# TDS_sensor_2.net
KiCad netlist of a schematic drawn in Altium Designer
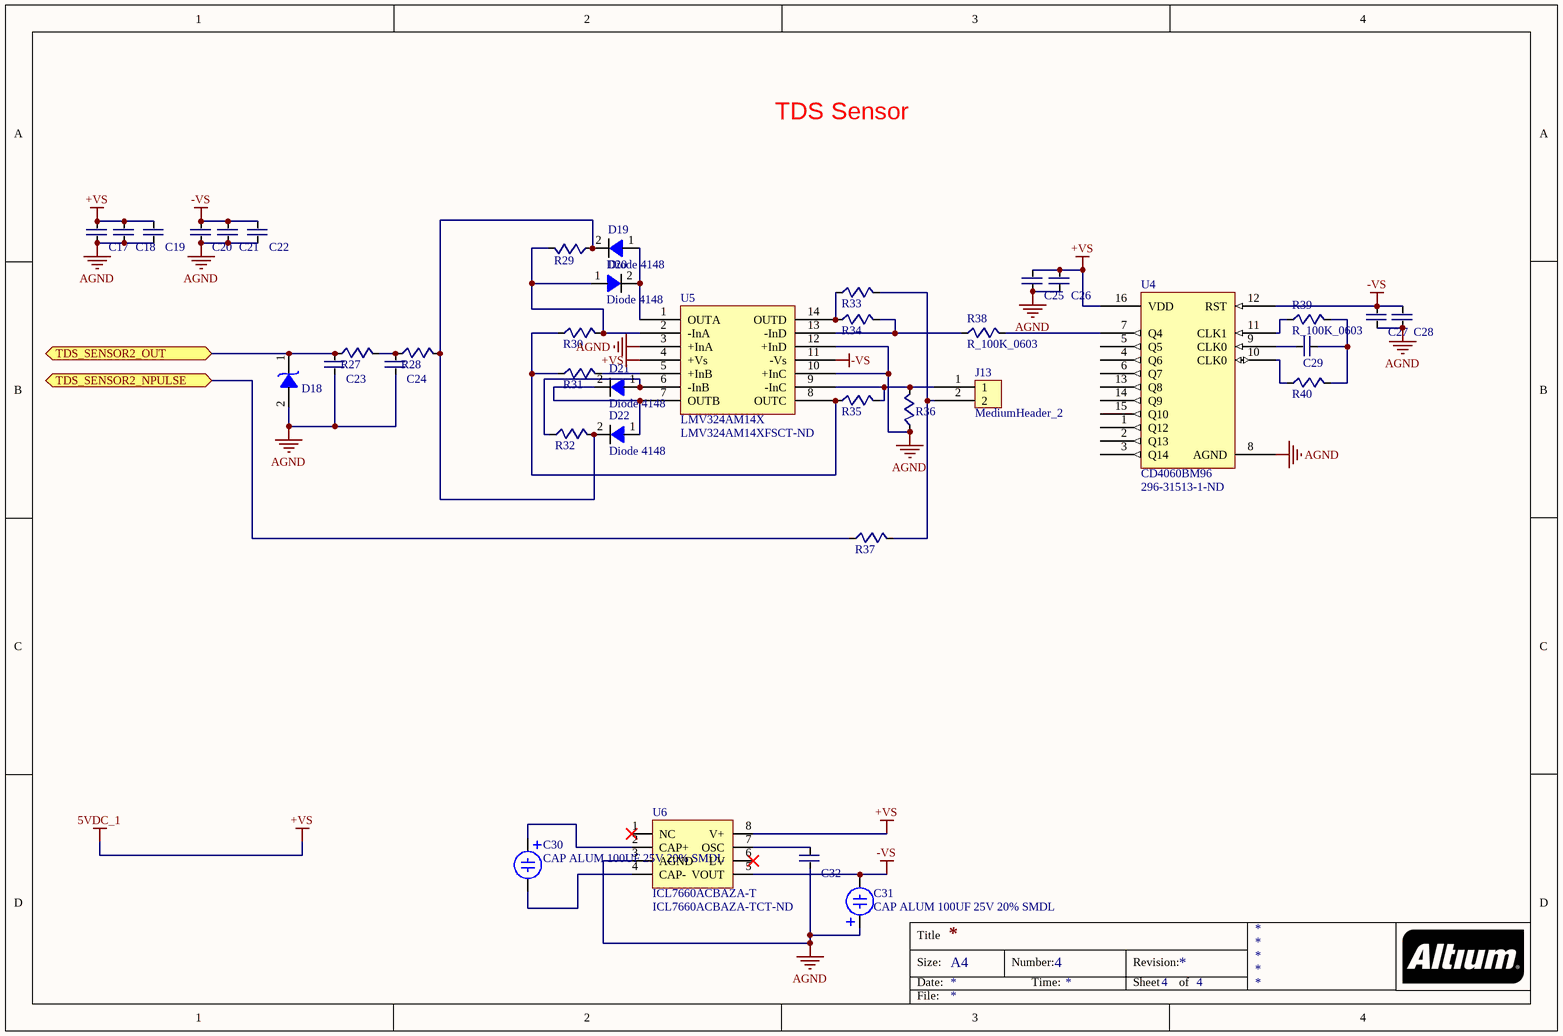
[diagram p0: TDS sensor 2.SchDoc]

(export (version "E")
  (design (tool "Eeschema 10.0.6"))
  (components
    (comp (ref "C17")
      (value "100n Cer")
      (footprint "CN-SMD-0805")
      (description "CAP CER 0.1UF 25V 10% X7R 0805")
      (libsource (lib "EngineersLife") (part "CAPC0805_104"))
    )
    (comp (ref "C18")
      (value "1n Cer")
      (footprint "CN-SMD-0805")
      (description "CAP CER 1000PF 50V 10% X7R 0805")
      (libsource (lib "EngineersLife") (part "CAPC0805_102"))
    )
    (comp (ref "C19")
      (value "10n Cer")
      (footprint "CN-SMD-0805")
      (description "CAP CER 10000PF 100V X7R 0805")
      (libsource (lib "EngineersLife") (part "CAPC0805_103"))
    )
    (comp (ref "C20")
      (value "100n Cer")
      (footprint "CN-SMD-0805")
      (description "CAP CER 0.1UF 25V 10% X7R 0805")
      (libsource (lib "EngineersLife") (part "CAPC0805_104"))
    )
    (comp (ref "C21")
      (value "1n Cer")
      (footprint "CN-SMD-0805")
      (description "CAP CER 1000PF 50V 10% X7R 0805")
      (libsource (lib "EngineersLife") (part "CAPC0805_102"))
    )
    (comp (ref "C22")
      (value "10n Cer")
      (footprint "CN-SMD-0805")
      (description "CAP CER 10000PF 100V X7R 0805")
      (libsource (lib "EngineersLife") (part "CAPC0805_103"))
    )
    (comp (ref "C23")
      (value "10u Cer")
      (footprint "CN-SMD-0805")
      (description "CAP CER 10UF 6.3V 10% X7R 0805")
      (libsource (lib "EngineersLife") (part "CAPC0805_106"))
    )
    (comp (ref "C24")
      (value "10u Cer")
      (footprint "CN-SMD-0805")
      (description "CAP CER 10UF 6.3V 10% X7R 0805")
      (libsource (lib "EngineersLife") (part "CAPC0805_106"))
    )
    (comp (ref "C25")
      (value "10n Cer")
      (footprint "CN-SMD-0805")
      (description "CAP CER 10000PF 100V X7R 0805")
      (libsource (lib "EngineersLife") (part "CAPC0805_103"))
    )
    (comp (ref "C26")
      (value "100n Cer")
      (footprint "CN-SMD-0805")
      (description "CAP CER 0.1UF 25V 10% X7R 0805")
      (libsource (lib "EngineersLife") (part "CAPC0805_104"))
    )
    (comp (ref "C27")
      (value "10n Cer")
      (footprint "CN-SMD-0805")
      (description "CAP CER 10000PF 100V X7R 0805")
      (libsource (lib "EngineersLife") (part "CAPC0805_103"))
    )
    (comp (ref "C28")
      (value "100n Cer")
      (footprint "CN-SMD-0805")
      (description "CAP CER 0.1UF 25V 10% X7R 0805")
      (libsource (lib "EngineersLife") (part "CAPC0805_104"))
    )
    (comp (ref "C29")
      (value "1n Cer")
      (footprint "CN-SMD-0805")
      (description "CAP CER 1000PF 50V 10% X7R 0805")
      (libsource (lib "EngineersLife") (part "CAPC0805_102"))
    )
    (comp (ref "C30")
      (value "CAP ALUM 100UF 25V 20% SMDL")
      (footprint "CAPALU_SM_5.3x5.3")
      (description "CAP ALUM 100UF 25V 20% SMD")
      (libsource (lib "EngineersLife") (part "CAPALU100U25V"))
    )
    (comp (ref "C31")
      (value "CAP ALUM 100UF 25V 20% SMDL")
      (footprint "CAPALU_SM_5.3x5.3")
      (description "CAP ALUM 100UF 25V 20% SMD")
      (libsource (lib "EngineersLife") (part "CAPALU100U25V"))
    )
    (comp (ref "C32")
      (value "100n Cer")
      (footprint "CN-SMD-0805")
      (description "CAP CER 0.1UF 25V 10% X7R 0805")
      (libsource (lib "EngineersLife") (part "CAPC0805_104"))
    )
    (comp (ref "D18")
      (value "Diode_SS34")
      (footprint "DO-214AB_MOD_EXT")
      (description "DIODE SCHOTTKY 40V 3A SMC")
      (libsource (lib "EngineersLife") (part "Diode_SS34"))
    )
    (comp (ref "D19")
      (value "Diode 4148")
      (footprint "CD3216-1206")
      (description "DIODE SWITCHING 75V 0.2A LLDS")
      (libsource (lib "EngineersLife") (part "Diode_4148"))
    )
    (comp (ref "D20")
      (value "Diode 4148")
      (footprint "CD3216-1206")
      (description "DIODE SWITCHING 75V 0.2A LLDS")
      (libsource (lib "EngineersLife") (part "Diode_4148"))
    )
    (comp (ref "D21")
      (value "Diode 4148")
      (footprint "CD3216-1206")
      (description "DIODE SWITCHING 75V 0.2A LLDS")
      (libsource (lib "EngineersLife") (part "Diode_4148"))
    )
    (comp (ref "D22")
      (value "Diode 4148")
      (footprint "CD3216-1206")
      (description "DIODE SWITCHING 75V 0.2A LLDS")
      (libsource (lib "EngineersLife") (part "Diode_4148"))
    )
    (comp (ref "J13")
      (value "MediumHeader_2")
      (footprint "Medium - Header 2")
      (libsource (lib "EngineersLife") (part "MediumHeader_2"))
    )
    (comp (ref "R27")
      (value "R_10K_0603")
      (footprint "RES-SMD-0603")
      (description "RES 10.0K OHM 1/10W 1% 0603 SMD")
      (libsource (lib "EngineersLife") (part "RES0603_10K"))
    )
    (comp (ref "R28")
      (value "R_10K_0603")
      (footprint "RES-SMD-0603")
      (description "RES 10.0K OHM 1/10W 1% 0603 SMD")
      (libsource (lib "EngineersLife") (part "RES0603_10K"))
    )
    (comp (ref "R29")
      (value "R_10K_0603")
      (footprint "RES-SMD-0603")
      (description "RES 10.0K OHM 1/10W 1% 0603 SMD")
      (libsource (lib "EngineersLife") (part "RES0603_10K"))
    )
    (comp (ref "R30")
      (value "R_10K_0603")
      (footprint "RES-SMD-0603")
      (description "RES 10.0K OHM 1/10W 1% 0603 SMD")
      (libsource (lib "EngineersLife") (part "RES0603_10K"))
    )
    (comp (ref "R31")
      (value "R_10K_0603")
      (footprint "RES-SMD-0603")
      (description "RES 10.0K OHM 1/10W 1% 0603 SMD")
      (libsource (lib "EngineersLife") (part "RES0603_10K"))
    )
    (comp (ref "R32")
      (value "R_10K_0603")
      (footprint "RES-SMD-0603")
      (description "RES 10.0K OHM 1/10W 1% 0603 SMD")
      (libsource (lib "EngineersLife") (part "RES0603_10K"))
    )
    (comp (ref "R33")
      (value "R_0R_0603")
      (footprint "RES-SMD-0603")
      (description "RES 0.0 OHM 1/10W JUMP 0603 SMD")
      (libsource (lib "EngineersLife") (part "RES0603_0R"))
    )
    (comp (ref "R34")
      (value "R_4K99_0603")
      (footprint "RES-SMD-0603")
      (description "RES 4.99K OHM 1/10W 1% 0603 SMD")
      (libsource (lib "EngineersLife") (part "RES0603_4K99"))
    )
    (comp (ref "R35")
      (value "R_4K99_0603")
      (footprint "RES-SMD-0603")
      (description "RES 4.99K OHM 1/10W 1% 0603 SMD")
      (libsource (lib "EngineersLife") (part "RES0603_4K99"))
    )
    (comp (ref "R36")
      (value "R_1M_0603")
      (footprint "RES-SMD-0603")
      (description "RES 1M OHM 1/8W 1% 0603 SMD")
      (libsource (lib "EngineersLife") (part "RES0603_1M"))
    )
    (comp (ref "R37")
      (value "R_0R_0603")
      (footprint "RES-SMD-0603")
      (description "RES 0.0 OHM 1/10W JUMP 0603 SMD")
      (libsource (lib "EngineersLife") (part "RES0603_0R"))
    )
    (comp (ref "R38")
      (value "R_100K_0603")
      (footprint "RES-SMD-0603")
      (description "RES 100K OHM 1/10W 1% 0603 SMD")
      (libsource (lib "EngineersLife") (part "RES0603_100K"))
    )
    (comp (ref "R39")
      (value "R_100K_0603")
      (footprint "RES-SMD-0603")
      (description "RES 100K OHM 1/10W 1% 0603 SMD")
      (libsource (lib "EngineersLife") (part "RES0603_100K"))
    )
    (comp (ref "R40")
      (value "R_10K_0603")
      (footprint "RES-SMD-0603")
      (description "RES 10.0K OHM 1/10W 1% 0603 SMD")
      (libsource (lib "EngineersLife") (part "RES0603_10K"))
    )
    (comp (ref "U4")
      (value "CD4060BM96")
      (footprint "SOIC_16")
      (description "IC BINARY COUNTER/DIV/OSC 16SOIC")
      (fields (field (name "SUPPLIER PART NUMBER 1") "296-31513-1-ND"))
      (libsource (lib "EngineersLife") (part "CD4060BM"))
    )
    (comp (ref "U5")
      (value "LMV324AM14X")
      (footprint "SOIC-14")
      (description "IC OPAMP VFB 1.4MHZ RRO 14SOIC")
      (fields (field (name "SUPPLIER PART NUMBER 1") "LMV324AM14XFSCT-ND"))
      (libsource (lib "EngineersLife") (part "LMV324A"))
    )
    (comp (ref "U6")
      (value "ICL7660ACBAZA-T")
      (footprint "SOIC-8_MOD_24LC128")
      (description "IC REG SWTCHD CAP INV 45MA 8SOIC")
      (fields
        (field (name "SUPPLIER PART NUMBER 1") "ICL7660ACBAZA-TCT-ND")
        (field (name "CREATOR") "Nguyen Ba Bien")
      )
      (libsource (lib "EngineersLife") (part "ICL7660"))
    )
  )
  (nets
    (net (code "1") (name "+VS") (class "Default")
      (node (ref "C17") (pin "2") (pinfunction "2_2") (pintype "passive"))
      (node (ref "C18") (pin "2") (pinfunction "2_2") (pintype "passive"))
      (node (ref "C19") (pin "2") (pinfunction "2_2") (pintype "passive"))
      (node (ref "C25") (pin "2") (pinfunction "2_2") (pintype "passive"))
      (node (ref "C26") (pin "2") (pinfunction "2_2") (pintype "passive"))
      (node (ref "U4") (pin "16") (pinfunction "VDD_16") (pintype "power_in"))
      (node (ref "U5") (pin "4") (pinfunction "+Vs_4") (pintype "passive"))
      (node (ref "U6") (pin "8") (pinfunction "V+_8") (pintype "passive"))
    )
    (net (code "2") (name "-VS") (class "Default")
      (node (ref "C20") (pin "2") (pinfunction "2_2") (pintype "passive"))
      (node (ref "C21") (pin "2") (pinfunction "2_2") (pintype "passive"))
      (node (ref "C22") (pin "2") (pinfunction "2_2") (pintype "passive"))
      (node (ref "C27") (pin "2") (pinfunction "2_2") (pintype "passive"))
      (node (ref "C28") (pin "2") (pinfunction "2_2") (pintype "passive"))
      (node (ref "C31") (pin "2") (pinfunction "2_2") (pintype "passive"))
      (node (ref "U4") (pin "12") (pinfunction "RST_12") (pintype "input"))
      (node (ref "U5") (pin "11") (pinfunction "-Vs_11") (pintype "passive"))
      (node (ref "U6") (pin "5") (pinfunction "VOUT_5") (pintype "passive"))
    )
    (net (code "3") (name "/TDS_SENSOR2_NPULSE") (class "Default")
      (node (ref "R37") (pin "1") (pinfunction "1_1") (pintype "passive"))
    )
    (net (code "4") (name "/TDS_SENSOR2_OUT") (class "Default")
      (node (ref "C23") (pin "2") (pinfunction "2_2") (pintype "passive"))
      (node (ref "D18") (pin "1") (pinfunction "1_1") (pintype "passive"))
      (node (ref "R27") (pin "1") (pinfunction "1_1") (pintype "passive"))
    )
    (net (code "5") (name "AGND") (class "Default")
      (node (ref "C17") (pin "1") (pinfunction "1_1") (pintype "passive"))
      (node (ref "C18") (pin "1") (pinfunction "1_1") (pintype "passive"))
      (node (ref "C19") (pin "1") (pinfunction "1_1") (pintype "passive"))
      (node (ref "C20") (pin "1") (pinfunction "1_1") (pintype "passive"))
      (node (ref "C21") (pin "1") (pinfunction "1_1") (pintype "passive"))
      (node (ref "C22") (pin "1") (pinfunction "1_1") (pintype "passive"))
      (node (ref "C23") (pin "1") (pinfunction "1_1") (pintype "passive"))
      (node (ref "C24") (pin "1") (pinfunction "1_1") (pintype "passive"))
      (node (ref "C25") (pin "1") (pinfunction "1_1") (pintype "passive"))
      (node (ref "C26") (pin "1") (pinfunction "1_1") (pintype "passive"))
      (node (ref "C27") (pin "1") (pinfunction "1_1") (pintype "passive"))
      (node (ref "C28") (pin "1") (pinfunction "1_1") (pintype "passive"))
      (node (ref "C31") (pin "1") (pinfunction "1_1") (pintype "passive"))
      (node (ref "C32") (pin "1") (pinfunction "1_1") (pintype "passive"))
      (node (ref "D18") (pin "2") (pinfunction "2_2") (pintype "passive"))
      (node (ref "R36") (pin "1") (pinfunction "1_1") (pintype "passive"))
      (node (ref "U4") (pin "8") (pinfunction "AGND_8") (pintype "power_in"))
      (node (ref "U5") (pin "10") (pinfunction "+InC_10") (pintype "passive"))
      (node (ref "U5") (pin "12") (pinfunction "+InD_12") (pintype "passive"))
      (node (ref "U5") (pin "3") (pinfunction "+InA_3") (pintype "passive"))
      (node (ref "U6") (pin "3") (pinfunction "AGND_3") (pintype "passive"))
    )
    (net (code "6") (name "Net-(C24-Pad2)") (class "Default")
      (node (ref "C24") (pin "2") (pinfunction "2_2") (pintype "passive"))
      (node (ref "R27") (pin "2") (pinfunction "2_2") (pintype "passive"))
      (node (ref "R28") (pin "1") (pinfunction "1_1") (pintype "passive"))
    )
    (net (code "7") (name "Net-(C29-Pad1)") (class "Default")
      (node (ref "C29") (pin "1") (pinfunction "1_1") (pintype "passive"))
      (node (ref "U4") (pin "9") (pinfunction "CLK0_9") (pintype "input"))
    )
    (net (code "8") (name "Net-(C29-Pad2)") (class "Default")
      (node (ref "C29") (pin "2") (pinfunction "2_2") (pintype "passive"))
      (node (ref "R39") (pin "2") (pinfunction "2_2") (pintype "passive"))
      (node (ref "R40") (pin "2") (pinfunction "2_2") (pintype "passive"))
    )
    (net (code "9") (name "Net-(D19-3)") (class "Default")
      (node (ref "D19") (pin "1") (pinfunction "3_1") (pintype "passive"))
      (node (ref "D20") (pin "2") (pinfunction "4_2") (pintype "passive"))
      (node (ref "U5") (pin "1") (pinfunction "OUTA_1") (pintype "passive"))
    )
    (net (code "10") (name "Net-(D19-4)") (class "Default")
      (node (ref "D19") (pin "2") (pinfunction "4_2") (pintype "passive"))
      (node (ref "D22") (pin "2") (pinfunction "4_2") (pintype "passive"))
      (node (ref "R28") (pin "2") (pinfunction "2_2") (pintype "passive"))
      (node (ref "R29") (pin "1") (pinfunction "1_1") (pintype "passive"))
      (node (ref "R32") (pin "2") (pinfunction "2_2") (pintype "passive"))
    )
    (net (code "11") (name "Net-(D20-3)") (class "Default")
      (node (ref "D20") (pin "1") (pinfunction "3_1") (pintype "passive"))
      (node (ref "R29") (pin "2") (pinfunction "2_2") (pintype "passive"))
      (node (ref "R30") (pin "2") (pinfunction "2_2") (pintype "passive"))
      (node (ref "U5") (pin "2") (pinfunction "-InA_2") (pintype "passive"))
    )
    (net (code "12") (name "Net-(D21-3)") (class "Default")
      (node (ref "D21") (pin "1") (pinfunction "3_1") (pintype "passive"))
      (node (ref "R32") (pin "1") (pinfunction "1_1") (pintype "passive"))
      (node (ref "U5") (pin "6") (pinfunction "-InB_6") (pintype "passive"))
    )
    (net (code "13") (name "Net-(D21-4)") (class "Default")
      (node (ref "D21") (pin "2") (pinfunction "4_2") (pintype "passive"))
      (node (ref "D22") (pin "1") (pinfunction "3_1") (pintype "passive"))
      (node (ref "U5") (pin "7") (pinfunction "OUTB_7") (pintype "passive"))
    )
    (net (code "14") (name "Net-(J13-Pad2)") (class "Default")
      (node (ref "J13") (pin "2") (pinfunction "2_2") (pintype "passive"))
      (node (ref "R33") (pin "2") (pinfunction "2_2") (pintype "passive"))
      (node (ref "R37") (pin "2") (pinfunction "2_2") (pintype "passive"))
    )
    (net (code "15") (name "Net-(R40-Pad1)") (class "Default")
      (node (ref "R40") (pin "1") (pinfunction "1_1") (pintype "passive"))
      (node (ref "U4") (pin "10") (pinfunction "CLK0_10") (pintype "bidirectional"))
    )
    (net (code "16") (name "Net-(U4-CLK1)") (class "Default")
      (node (ref "R39") (pin "1") (pinfunction "1_1") (pintype "passive"))
      (node (ref "U4") (pin "11") (pinfunction "CLK1_11") (pintype "input"))
    )
    (net (code "17") (name "Net-(U4-Q4)") (class "Default")
      (node (ref "R38") (pin "2") (pinfunction "2_2") (pintype "passive"))
      (node (ref "U4") (pin "7") (pinfunction "Q4_7") (pintype "output"))
    )
    (net (code "18") (name "Net-(U5-+InB)") (class "Default")
      (node (ref "R31") (pin "2") (pinfunction "2_2") (pintype "passive"))
      (node (ref "U5") (pin "5") (pinfunction "+InB_5") (pintype "passive"))
    )
    (net (code "19") (name "Net-(U5--InC)") (class "Default")
      (node (ref "J13") (pin "1") (pinfunction "1_1") (pintype "passive"))
      (node (ref "R35") (pin "2") (pinfunction "2_2") (pintype "passive"))
      (node (ref "R36") (pin "2") (pinfunction "2_2") (pintype "passive"))
      (node (ref "U5") (pin "9") (pinfunction "-InC_9") (pintype "passive"))
    )
    (net (code "20") (name "Net-(U5--InD)") (class "Default")
      (node (ref "R34") (pin "2") (pinfunction "2_2") (pintype "passive"))
      (node (ref "R38") (pin "1") (pinfunction "1_1") (pintype "passive"))
      (node (ref "U5") (pin "13") (pinfunction "-InD_13") (pintype "passive"))
    )
    (net (code "21") (name "Net-(U5-OUTC)") (class "Default")
      (node (ref "R30") (pin "1") (pinfunction "1_1") (pintype "passive"))
      (node (ref "R31") (pin "1") (pinfunction "1_1") (pintype "passive"))
      (node (ref "R35") (pin "1") (pinfunction "1_1") (pintype "passive"))
      (node (ref "U5") (pin "8") (pinfunction "OUTC_8") (pintype "passive"))
    )
    (net (code "22") (name "Net-(U5-OUTD)") (class "Default")
      (node (ref "R33") (pin "1") (pinfunction "1_1") (pintype "passive"))
      (node (ref "R34") (pin "1") (pinfunction "1_1") (pintype "passive"))
      (node (ref "U5") (pin "14") (pinfunction "OUTD_14") (pintype "passive"))
    )
    (net (code "23") (name "Net-(U6-CAP+)") (class "Default")
      (node (ref "C30") (pin "1") (pinfunction "1_1") (pintype "passive"))
      (node (ref "U6") (pin "2") (pinfunction "CAP+_2") (pintype "passive"))
    )
    (net (code "24") (name "Net-(U6-CAP-)") (class "Default")
      (node (ref "C30") (pin "2") (pinfunction "2_2") (pintype "passive"))
      (node (ref "U6") (pin "4") (pinfunction "CAP-_4") (pintype "passive"))
    )
    (net (code "25") (name "Net-(U6-OSC)") (class "Default")
      (node (ref "C32") (pin "2") (pinfunction "2_2") (pintype "passive"))
      (node (ref "U6") (pin "7") (pinfunction "OSC_7") (pintype "passive"))
    )
    (net (code "26") (name "unconnected-(U4-Q5-Pad5)") (class "Default")
      (node (ref "U4") (pin "5") (pinfunction "Q5_5") (pintype "output"))
    )
    (net (code "27") (name "unconnected-(U4-Q6-Pad4)") (class "Default")
      (node (ref "U4") (pin "4") (pinfunction "Q6_4") (pintype "output"))
    )
    (net (code "28") (name "unconnected-(U4-Q7-Pad6)") (class "Default")
      (node (ref "U4") (pin "6") (pinfunction "Q7_6") (pintype "output"))
    )
    (net (code "29") (name "unconnected-(U4-Q8-Pad13)") (class "Default")
      (node (ref "U4") (pin "13") (pinfunction "Q8_13") (pintype "output"))
    )
    (net (code "30") (name "unconnected-(U4-Q9-Pad14)") (class "Default")
      (node (ref "U4") (pin "14") (pinfunction "Q9_14") (pintype "output"))
    )
    (net (code "31") (name "unconnected-(U4-Q10-Pad15)") (class "Default")
      (node (ref "U4") (pin "15") (pinfunction "Q10_15") (pintype "output"))
    )
    (net (code "32") (name "unconnected-(U4-Q12-Pad1)") (class "Default")
      (node (ref "U4") (pin "1") (pinfunction "Q12_1") (pintype "output"))
    )
    (net (code "33") (name "unconnected-(U4-Q13-Pad2)") (class "Default")
      (node (ref "U4") (pin "2") (pinfunction "Q13_2") (pintype "output"))
    )
    (net (code "34") (name "unconnected-(U4-Q14-Pad3)") (class "Default")
      (node (ref "U4") (pin "3") (pinfunction "Q14_3") (pintype "output"))
    )
    (net (code "35") (name "unconnected-(U6-LV-Pad6)") (class "Default")
      (node (ref "U6") (pin "6") (pinfunction "LV_6") (pintype "passive+no_connect"))
    )
    (net (code "36") (name "unconnected-(U6-NC-Pad1)") (class "Default")
      (node (ref "U6") (pin "1") (pinfunction "NC_1") (pintype "passive+no_connect"))
    )
  )
)
